# Adafruit_CyberDeck_Bonnet.net
KiCad netlist of a schematic drawn in EAGLE
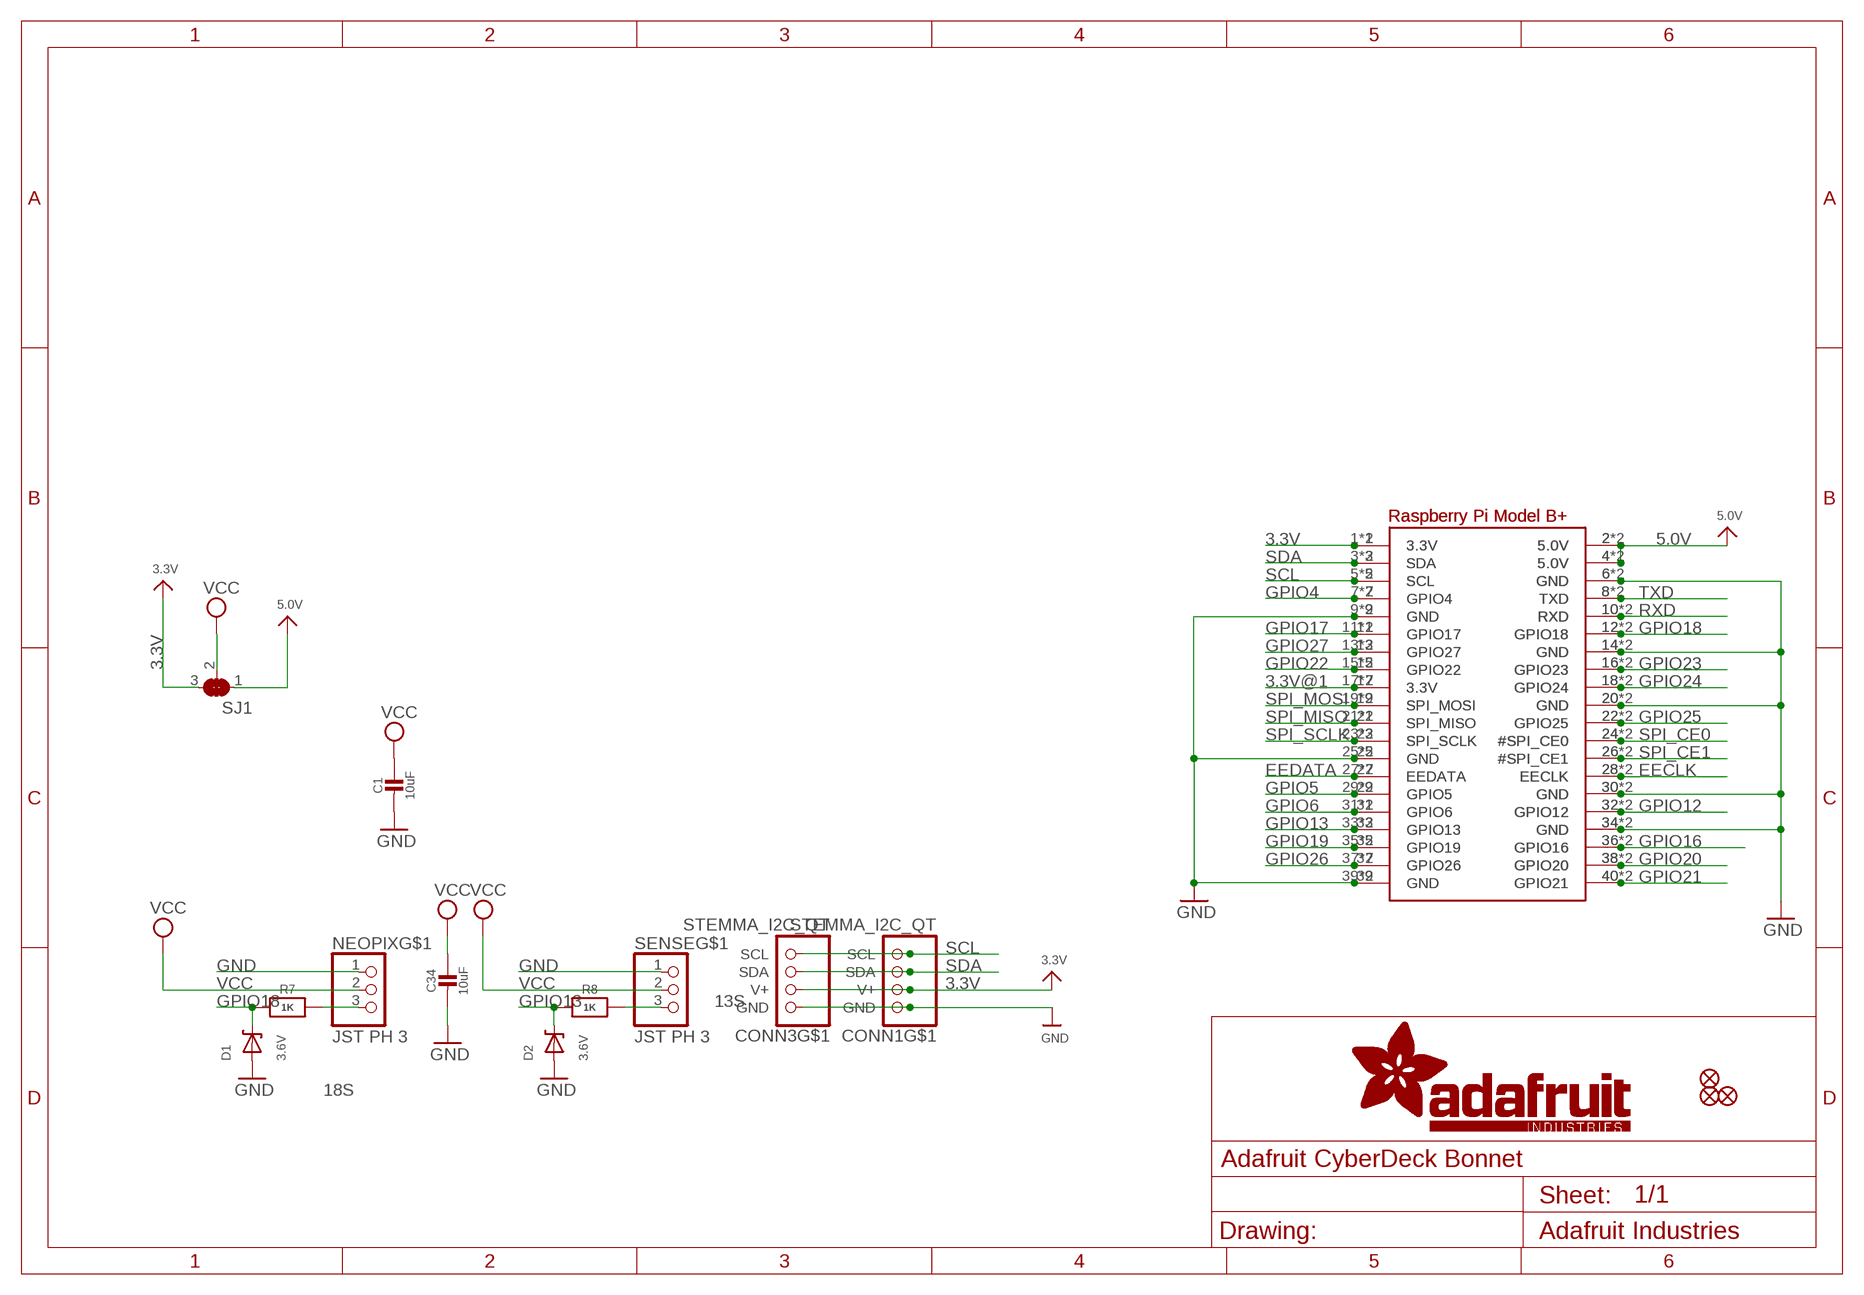
[diagram p0: schematic, sheet 1]

(export (version "E")
  (design (tool "Eeschema 10.0.6"))
  (components
    (comp (ref "C1")
      (value "10uF")
      (footprint "eagle-import:0805-NO")
      (libsource (lib "eagle-import") (part "CAP_CERAMIC0805-NOOUTLINE"))
    )
    (comp (ref "C34")
      (value "10uF")
      (footprint "eagle-import:0805-NO")
      (libsource (lib "eagle-import") (part "CAP_CERAMIC0805-NOOUTLINE"))
    )
    (comp (ref "CONN1")
      (value "STEMMA_I2C_QT")
      (footprint "eagle-import:JST_SH4")
      (libsource (lib "eagle-import") (part "STEMMA_I2C_QT"))
    )
    (comp (ref "CONN3")
      (value "STEMMA_I2C_QT")
      (footprint "eagle-import:JST_SH4")
      (libsource (lib "eagle-import") (part "STEMMA_I2C_QT"))
    )
    (comp (ref "D1")
      (value "3.6V")
      (footprint "eagle-import:SOD-323")
      (libsource (lib "eagle-import") (part "DIODE-ZENERSOD323"))
    )
    (comp (ref "D2")
      (value "3.6V")
      (footprint "eagle-import:SOD-323")
      (libsource (lib "eagle-import") (part "DIODE-ZENERSOD323"))
    )
    (comp (ref "FID1")
      (value "FIDUCIAL_1MM")
      (footprint "eagle-import:FIDUCIAL_1MM")
      (libsource (lib "eagle-import") (part "FIDUCIAL_1MM"))
    )
    (comp (ref "FID2")
      (value "FIDUCIAL_1MM")
      (footprint "eagle-import:FIDUCIAL_1MM")
      (libsource (lib "eagle-import") (part "FIDUCIAL_1MM"))
    )
    (comp (ref "FID3")
      (value "FIDUCIAL_1MM")
      (footprint "eagle-import:FIDUCIAL_1MM")
      (libsource (lib "eagle-import") (part "FIDUCIAL_1MM"))
    )
    (comp (ref "NEOPIX")
      (value "JST PH 3")
      (footprint "eagle-import:JSTPH3")
      (libsource (lib "eagle-import") (part "CON_JST_PH_3PIN"))
    )
    (comp (ref "R7")
      (value "1K")
      (footprint "eagle-import:0603-NO")
      (libsource (lib "eagle-import") (part "RESISTOR_0603_NOOUT"))
    )
    (comp (ref "R8")
      (value "1K")
      (footprint "eagle-import:0603-NO")
      (libsource (lib "eagle-import") (part "RESISTOR_0603_NOOUT"))
    )
    (comp (ref "RPI1")
      (value "RASPBERRYPI_BPLUS_IDC")
      (footprint "eagle-import:2X20")
      (libsource (lib "eagle-import") (part "RASPBERRYPI_BPLUS_IDC"))
    )
    (comp (ref "RPI2")
      (value "RASPBERRYPI_BPLUS_2X20_THMSMT_TOP")
      (footprint "eagle-import:RASPI_2X20_THMSMT_TOP")
      (libsource (lib "eagle-import") (part "RASPBERRYPI_BPLUS_2X20_THMSMT_TOP"))
    )
    (comp (ref "SENSE")
      (value "JST PH 3")
      (footprint "eagle-import:JSTPH3")
      (libsource (lib "eagle-import") (part "CON_JST_PH_3PIN"))
    )
    (comp (ref "SJ1")
      (value "SOLDERJUMPER_2WAY")
      (footprint "eagle-import:SOLDERJUMPER_2WAY_OPEN_NOPASTE")
      (libsource (lib "eagle-import") (part "SOLDERJUMPER_2WAY"))
    )
  )
  (nets
    (net (code "1") (name "/3.3V@1") (class "Default")
      (node (ref "RPI1") (pin "17") (pinfunction "3.3V_17") (pintype "power_in"))
      (node (ref "RPI2") (pin "17") (pinfunction "3.3V_17") (pintype "power_in"))
      (node (ref "RPI2") (pin "S17") (pinfunction "3.3V_S17") (pintype "power_in"))
    )
    (net (code "2") (name "/13S") (class "Default")
      (node (ref "R8") (pin "1") (pinfunction "1_1") (pintype "passive"))
      (node (ref "SENSE") (pin "3") (pinfunction "3_3") (pintype "passive"))
    )
    (net (code "3") (name "/18S") (class "Default")
      (node (ref "NEOPIX") (pin "3") (pinfunction "3_3") (pintype "passive"))
      (node (ref "R7") (pin "1") (pinfunction "1_1") (pintype "passive"))
    )
    (net (code "4") (name "/EECLK") (class "Default")
      (node (ref "RPI1") (pin "28") (pinfunction "EECLK_28") (pintype "bidirectional"))
      (node (ref "RPI2") (pin "28") (pinfunction "EECLK_28") (pintype "bidirectional"))
      (node (ref "RPI2") (pin "S28") (pinfunction "EECLK_S28") (pintype "bidirectional"))
    )
    (net (code "5") (name "/EEDATA") (class "Default")
      (node (ref "RPI1") (pin "27") (pinfunction "EEDATA_27") (pintype "bidirectional"))
      (node (ref "RPI2") (pin "27") (pinfunction "EEDATA_27") (pintype "bidirectional"))
      (node (ref "RPI2") (pin "S27") (pinfunction "EEDATA_S27") (pintype "bidirectional"))
    )
    (net (code "6") (name "/GPIO4") (class "Default")
      (node (ref "RPI1") (pin "7") (pinfunction "GPIO4_7") (pintype "bidirectional"))
      (node (ref "RPI2") (pin "7") (pinfunction "GPIO4_7") (pintype "bidirectional"))
      (node (ref "RPI2") (pin "S7") (pinfunction "GPIO4_S7") (pintype "bidirectional"))
    )
    (net (code "7") (name "/GPIO5") (class "Default")
      (node (ref "RPI1") (pin "29") (pinfunction "GPIO5_29") (pintype "bidirectional"))
      (node (ref "RPI2") (pin "29") (pinfunction "GPIO5_29") (pintype "bidirectional"))
      (node (ref "RPI2") (pin "S29") (pinfunction "GPIO5_S29") (pintype "bidirectional"))
    )
    (net (code "8") (name "/GPIO6") (class "Default")
      (node (ref "RPI1") (pin "31") (pinfunction "GPIO6_31") (pintype "bidirectional"))
      (node (ref "RPI2") (pin "31") (pinfunction "GPIO6_31") (pintype "bidirectional"))
      (node (ref "RPI2") (pin "S31") (pinfunction "GPIO6_S31") (pintype "bidirectional"))
    )
    (net (code "9") (name "/GPIO12") (class "Default")
      (node (ref "RPI1") (pin "32") (pinfunction "GPIO12_32") (pintype "bidirectional"))
      (node (ref "RPI2") (pin "32") (pinfunction "GPIO12_32") (pintype "bidirectional"))
      (node (ref "RPI2") (pin "S32") (pinfunction "GPIO12_S32") (pintype "bidirectional"))
    )
    (net (code "10") (name "/GPIO13") (class "Default")
      (node (ref "D2") (pin "C") (pinfunction "C_C") (pintype "passive"))
      (node (ref "R8") (pin "2") (pinfunction "2_2") (pintype "passive"))
      (node (ref "RPI1") (pin "33") (pinfunction "GPIO13_33") (pintype "bidirectional"))
      (node (ref "RPI2") (pin "33") (pinfunction "GPIO13_33") (pintype "bidirectional"))
      (node (ref "RPI2") (pin "S33") (pinfunction "GPIO13_S33") (pintype "bidirectional"))
    )
    (net (code "11") (name "/GPIO16") (class "Default")
      (node (ref "RPI1") (pin "36") (pinfunction "GPIO16_36") (pintype "bidirectional"))
      (node (ref "RPI2") (pin "36") (pinfunction "GPIO16_36") (pintype "bidirectional"))
      (node (ref "RPI2") (pin "S36") (pinfunction "GPIO16_S36") (pintype "bidirectional"))
    )
    (net (code "12") (name "/GPIO17") (class "Default")
      (node (ref "RPI1") (pin "11") (pinfunction "GPIO17_11") (pintype "bidirectional"))
      (node (ref "RPI2") (pin "11") (pinfunction "GPIO17_11") (pintype "bidirectional"))
      (node (ref "RPI2") (pin "S11") (pinfunction "GPIO17_S11") (pintype "bidirectional"))
    )
    (net (code "13") (name "/GPIO18") (class "Default")
      (node (ref "D1") (pin "C") (pinfunction "C_C") (pintype "passive"))
      (node (ref "R7") (pin "2") (pinfunction "2_2") (pintype "passive"))
      (node (ref "RPI1") (pin "12") (pinfunction "GPIO18_12") (pintype "bidirectional"))
      (node (ref "RPI2") (pin "12") (pinfunction "GPIO18_12") (pintype "bidirectional"))
      (node (ref "RPI2") (pin "S12") (pinfunction "GPIO18_S12") (pintype "bidirectional"))
    )
    (net (code "14") (name "/GPIO19") (class "Default")
      (node (ref "RPI1") (pin "35") (pinfunction "GPIO19_35") (pintype "bidirectional"))
      (node (ref "RPI2") (pin "35") (pinfunction "GPIO19_35") (pintype "bidirectional"))
      (node (ref "RPI2") (pin "S35") (pinfunction "GPIO19_S35") (pintype "bidirectional"))
    )
    (net (code "15") (name "/GPIO20") (class "Default")
      (node (ref "RPI1") (pin "38") (pinfunction "GPIO20_38") (pintype "bidirectional"))
      (node (ref "RPI2") (pin "38") (pinfunction "GPIO20_38") (pintype "bidirectional"))
      (node (ref "RPI2") (pin "S38") (pinfunction "GPIO20_S38") (pintype "bidirectional"))
    )
    (net (code "16") (name "/GPIO21") (class "Default")
      (node (ref "RPI1") (pin "40") (pinfunction "GPIO21_40") (pintype "bidirectional"))
      (node (ref "RPI2") (pin "40") (pinfunction "GPIO21_40") (pintype "bidirectional"))
      (node (ref "RPI2") (pin "S40") (pinfunction "GPIO21_S40") (pintype "bidirectional"))
    )
    (net (code "17") (name "/GPIO22") (class "Default")
      (node (ref "RPI1") (pin "15") (pinfunction "GPIO22_15") (pintype "bidirectional"))
      (node (ref "RPI2") (pin "15") (pinfunction "GPIO22_15") (pintype "bidirectional"))
      (node (ref "RPI2") (pin "S15") (pinfunction "GPIO22_S15") (pintype "bidirectional"))
    )
    (net (code "18") (name "/GPIO23") (class "Default")
      (node (ref "RPI1") (pin "16") (pinfunction "GPIO23_16") (pintype "bidirectional"))
      (node (ref "RPI2") (pin "16") (pinfunction "GPIO23_16") (pintype "bidirectional"))
      (node (ref "RPI2") (pin "S16") (pinfunction "GPIO23_S16") (pintype "bidirectional"))
    )
    (net (code "19") (name "/GPIO24") (class "Default")
      (node (ref "RPI1") (pin "18") (pinfunction "GPIO24_18") (pintype "bidirectional"))
      (node (ref "RPI2") (pin "18") (pinfunction "GPIO24_18") (pintype "bidirectional"))
      (node (ref "RPI2") (pin "S18") (pinfunction "GPIO24_S18") (pintype "bidirectional"))
    )
    (net (code "20") (name "/GPIO25") (class "Default")
      (node (ref "RPI1") (pin "22") (pinfunction "GPIO25_22") (pintype "bidirectional"))
      (node (ref "RPI2") (pin "22") (pinfunction "GPIO25_22") (pintype "bidirectional"))
      (node (ref "RPI2") (pin "S22") (pinfunction "GPIO25_S22") (pintype "bidirectional"))
    )
    (net (code "21") (name "/GPIO26") (class "Default")
      (node (ref "RPI1") (pin "37") (pinfunction "GPIO26_37") (pintype "bidirectional"))
      (node (ref "RPI2") (pin "37") (pinfunction "GPIO26_37") (pintype "bidirectional"))
      (node (ref "RPI2") (pin "S37") (pinfunction "GPIO26_S37") (pintype "bidirectional"))
    )
    (net (code "22") (name "/GPIO27") (class "Default")
      (node (ref "RPI1") (pin "13") (pinfunction "GPIO27_13") (pintype "bidirectional"))
      (node (ref "RPI2") (pin "13") (pinfunction "GPIO27_13") (pintype "bidirectional"))
      (node (ref "RPI2") (pin "S13") (pinfunction "GPIO27_S13") (pintype "bidirectional"))
    )
    (net (code "23") (name "/RXD") (class "Default")
      (node (ref "RPI1") (pin "10") (pinfunction "RXD_10") (pintype "bidirectional"))
      (node (ref "RPI2") (pin "10") (pinfunction "RXD_10") (pintype "bidirectional"))
      (node (ref "RPI2") (pin "S10") (pinfunction "RXD_S10") (pintype "bidirectional"))
    )
    (net (code "24") (name "/SCL") (class "Default")
      (node (ref "CONN1") (pin "4") (pinfunction "SCL_4") (pintype "passive"))
      (node (ref "CONN3") (pin "4") (pinfunction "SCL_4") (pintype "passive"))
      (node (ref "RPI1") (pin "5") (pinfunction "SCL_5") (pintype "bidirectional"))
      (node (ref "RPI2") (pin "5") (pinfunction "SCL_5") (pintype "bidirectional"))
      (node (ref "RPI2") (pin "S5") (pinfunction "SCL_S5") (pintype "bidirectional"))
    )
    (net (code "25") (name "/SDA") (class "Default")
      (node (ref "CONN1") (pin "3") (pinfunction "SDA_3") (pintype "passive"))
      (node (ref "CONN3") (pin "3") (pinfunction "SDA_3") (pintype "passive"))
      (node (ref "RPI1") (pin "3") (pinfunction "SDA_3") (pintype "bidirectional"))
      (node (ref "RPI2") (pin "3") (pinfunction "SDA_3") (pintype "bidirectional"))
      (node (ref "RPI2") (pin "S3") (pinfunction "SDA_S3") (pintype "bidirectional"))
    )
    (net (code "26") (name "/SPI_CE0") (class "Default")
      (node (ref "RPI1") (pin "24") (pinfunction "#SPI_CE0_24") (pintype "bidirectional"))
      (node (ref "RPI2") (pin "24") (pinfunction "#SPI_CE0_24") (pintype "bidirectional"))
      (node (ref "RPI2") (pin "S24") (pinfunction "#SPI_CE0_S24") (pintype "bidirectional"))
    )
    (net (code "27") (name "/SPI_CE1") (class "Default")
      (node (ref "RPI1") (pin "26") (pinfunction "#SPI_CE1_26") (pintype "bidirectional"))
      (node (ref "RPI2") (pin "26") (pinfunction "#SPI_CE1_26") (pintype "bidirectional"))
      (node (ref "RPI2") (pin "S26") (pinfunction "#SPI_CE1_S26") (pintype "bidirectional"))
    )
    (net (code "28") (name "/SPI_MISO") (class "Default")
      (node (ref "RPI1") (pin "21") (pinfunction "SPI_MISO_21") (pintype "bidirectional"))
      (node (ref "RPI2") (pin "21") (pinfunction "SPI_MISO_21") (pintype "bidirectional"))
      (node (ref "RPI2") (pin "S21") (pinfunction "SPI_MISO_S21") (pintype "bidirectional"))
    )
    (net (code "29") (name "/SPI_MOSI") (class "Default")
      (node (ref "RPI1") (pin "19") (pinfunction "SPI_MOSI_19") (pintype "bidirectional"))
      (node (ref "RPI2") (pin "19") (pinfunction "SPI_MOSI_19") (pintype "bidirectional"))
      (node (ref "RPI2") (pin "S19") (pinfunction "SPI_MOSI_S19") (pintype "bidirectional"))
    )
    (net (code "30") (name "/SPI_SCLK") (class "Default")
      (node (ref "RPI1") (pin "23") (pinfunction "SPI_SCLK_23") (pintype "bidirectional"))
      (node (ref "RPI2") (pin "23") (pinfunction "SPI_SCLK_23") (pintype "bidirectional"))
      (node (ref "RPI2") (pin "S23") (pinfunction "SPI_SCLK_S23") (pintype "bidirectional"))
    )
    (net (code "31") (name "/TXD") (class "Default")
      (node (ref "RPI1") (pin "8") (pinfunction "TXD_8") (pintype "bidirectional"))
      (node (ref "RPI2") (pin "8") (pinfunction "TXD_8") (pintype "bidirectional"))
      (node (ref "RPI2") (pin "S8") (pinfunction "TXD_S8") (pintype "bidirectional"))
    )
    (net (code "32") (name "3.3V") (class "Default")
      (node (ref "CONN1") (pin "2") (pinfunction "V+_2") (pintype "passive"))
      (node (ref "CONN3") (pin "2") (pinfunction "V+_2") (pintype "passive"))
      (node (ref "RPI1") (pin "1") (pinfunction "3.3V_1") (pintype "power_in"))
      (node (ref "RPI2") (pin "1") (pinfunction "3.3V_1") (pintype "power_in"))
      (node (ref "RPI2") (pin "S1") (pinfunction "3.3V_S1") (pintype "power_in"))
      (node (ref "SJ1") (pin "3") (pinfunction "3_3") (pintype "passive"))
    )
    (net (code "33") (name "5.0V") (class "Default")
      (node (ref "RPI1") (pin "2") (pinfunction "5.0V_2") (pintype "power_in"))
      (node (ref "RPI1") (pin "4") (pinfunction "5.0V_4") (pintype "power_in"))
      (node (ref "RPI2") (pin "2") (pinfunction "5.0V_2") (pintype "power_in"))
      (node (ref "RPI2") (pin "4") (pinfunction "5.0V_4") (pintype "power_in"))
      (node (ref "RPI2") (pin "S2") (pinfunction "5.0V_S2") (pintype "power_in"))
      (node (ref "RPI2") (pin "S4") (pinfunction "5.0V_S4") (pintype "power_in"))
      (node (ref "SJ1") (pin "1") (pinfunction "1_1") (pintype "passive"))
    )
    (net (code "34") (name "GND") (class "Default")
      (node (ref "C1") (pin "2") (pinfunction "2_2") (pintype "passive"))
      (node (ref "C34") (pin "2") (pinfunction "2_2") (pintype "passive"))
      (node (ref "CONN1") (pin "1") (pinfunction "GND_1") (pintype "passive"))
      (node (ref "CONN3") (pin "1") (pinfunction "GND_1") (pintype "passive"))
      (node (ref "D1") (pin "A") (pinfunction "A_A") (pintype "passive"))
      (node (ref "D2") (pin "A") (pinfunction "A_A") (pintype "passive"))
      (node (ref "NEOPIX") (pin "1") (pinfunction "1_1") (pintype "passive"))
      (node (ref "RPI1") (pin "14") (pinfunction "GND_14") (pintype "power_in"))
      (node (ref "RPI1") (pin "20") (pinfunction "GND_20") (pintype "power_in"))
      (node (ref "RPI1") (pin "25") (pinfunction "GND_25") (pintype "power_in"))
      (node (ref "RPI1") (pin "30") (pinfunction "GND_30") (pintype "power_in"))
      (node (ref "RPI1") (pin "34") (pinfunction "GND_34") (pintype "power_in"))
      (node (ref "RPI1") (pin "39") (pinfunction "GND_39") (pintype "power_in"))
      (node (ref "RPI1") (pin "6") (pinfunction "GND_6") (pintype "power_in"))
      (node (ref "RPI1") (pin "9") (pinfunction "GND_9") (pintype "power_in"))
      (node (ref "RPI2") (pin "14") (pinfunction "GND_14") (pintype "power_in"))
      (node (ref "RPI2") (pin "20") (pinfunction "GND_20") (pintype "power_in"))
      (node (ref "RPI2") (pin "25") (pinfunction "GND_25") (pintype "power_in"))
      (node (ref "RPI2") (pin "30") (pinfunction "GND_30") (pintype "power_in"))
      (node (ref "RPI2") (pin "34") (pinfunction "GND_34") (pintype "power_in"))
      (node (ref "RPI2") (pin "39") (pinfunction "GND_39") (pintype "power_in"))
      (node (ref "RPI2") (pin "6") (pinfunction "GND_6") (pintype "power_in"))
      (node (ref "RPI2") (pin "9") (pinfunction "GND_9") (pintype "power_in"))
      (node (ref "RPI2") (pin "S14") (pinfunction "GND_S14") (pintype "power_in"))
      (node (ref "RPI2") (pin "S20") (pinfunction "GND_S20") (pintype "power_in"))
      (node (ref "RPI2") (pin "S25") (pinfunction "GND_S25") (pintype "power_in"))
      (node (ref "RPI2") (pin "S30") (pinfunction "GND_S30") (pintype "power_in"))
      (node (ref "RPI2") (pin "S34") (pinfunction "GND_S34") (pintype "power_in"))
      (node (ref "RPI2") (pin "S39") (pinfunction "GND_S39") (pintype "power_in"))
      (node (ref "RPI2") (pin "S6") (pinfunction "GND_S6") (pintype "power_in"))
      (node (ref "RPI2") (pin "S9") (pinfunction "GND_S9") (pintype "power_in"))
      (node (ref "SENSE") (pin "1") (pinfunction "1_1") (pintype "passive"))
    )
    (net (code "35") (name "VCC") (class "Default")
      (node (ref "C1") (pin "1") (pinfunction "1_1") (pintype "passive"))
      (node (ref "C34") (pin "1") (pinfunction "1_1") (pintype "passive"))
      (node (ref "NEOPIX") (pin "2") (pinfunction "2_2") (pintype "passive"))
      (node (ref "SENSE") (pin "2") (pinfunction "2_2") (pintype "passive"))
      (node (ref "SJ1") (pin "2") (pinfunction "2_2") (pintype "passive"))
    )
  )
)
